# board.net
KiCad netlist of a schematic drawn in EAGLE
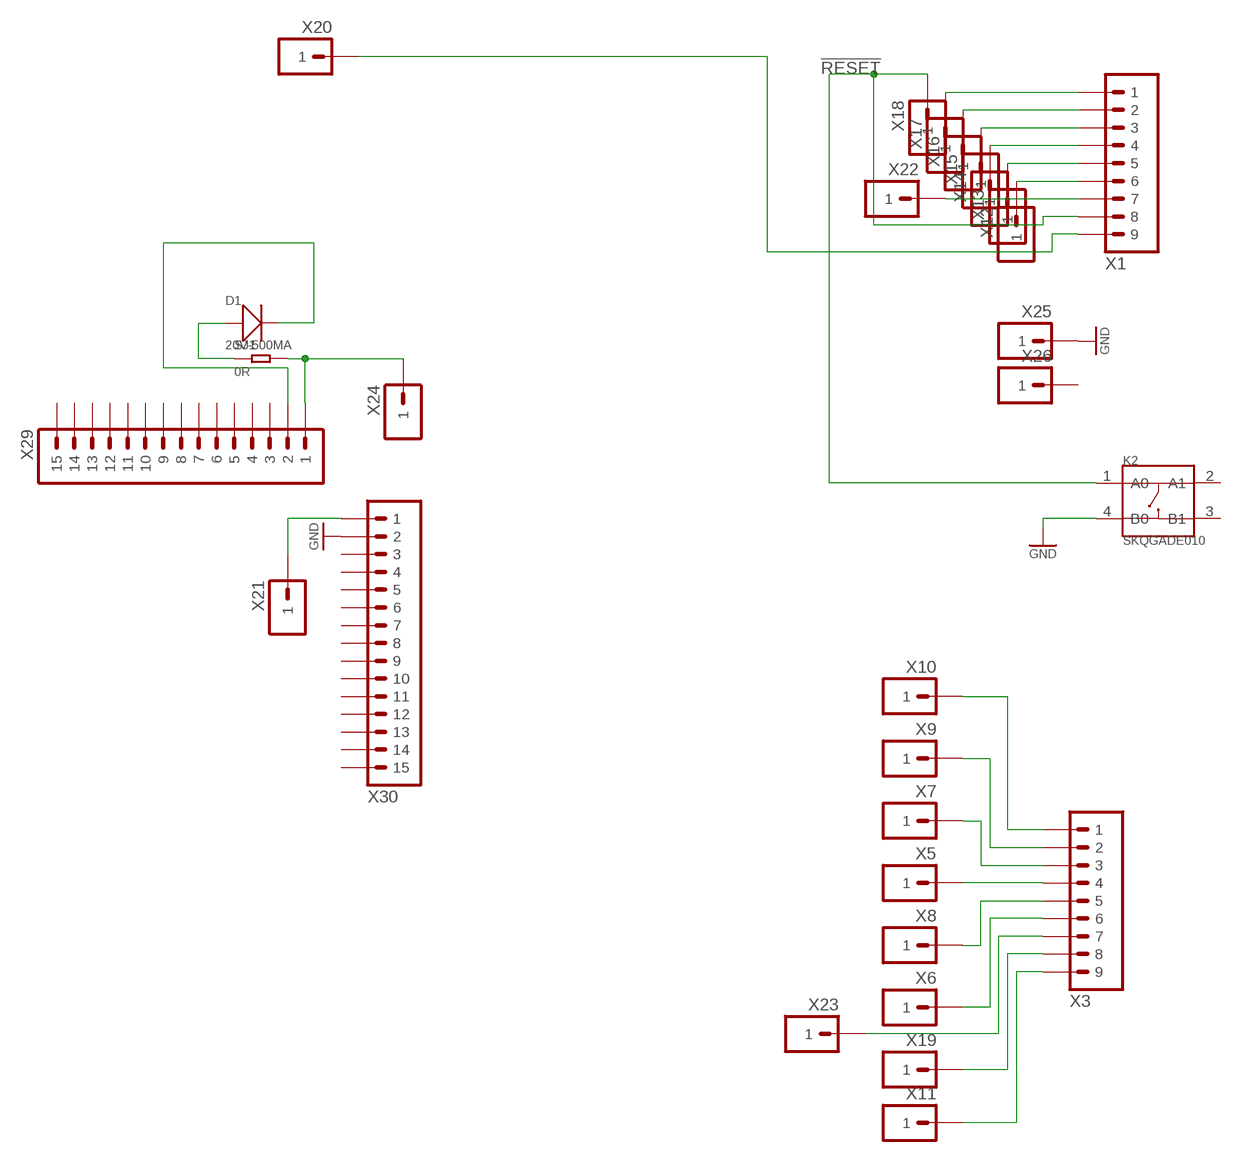
[diagram p0: schematic, sheet 1]

(export (version "E")
  (design (tool "Eeschema 10.0.6"))
  (components
    (comp (ref "D1")
      (value "20V-500MA")
      (footprint "eagle-import:SOD-123")
      (fields (field (name "MPN") "MBR0520LT1G"))
      (libsource (lib "eagle-import") (part "SMD-DIODE-SCHOTTKY-20V-500MA(SOD-123)"))
    )
    (comp (ref "K2")
      (value "SKQGADE010")
      (footprint "eagle-import:SW4-SMD-5.2X5.2X1.5MM")
      (libsource (lib "eagle-import") (part "SMD-SWITCH-TOP-260GF(4P-D5.2MM)"))
    )
    (comp (ref "SJ1")
      (value "0R")
      (footprint "eagle-import:R0805")
      (fields (field (name "MPN") "RC0805FR-071K5L"))
      (libsource (lib "eagle-import") (part "SMD-RES-1.5K-1%-1/8W(0805)"))
    )
    (comp (ref "X1")
      (value "9P1/MIN_NOSILK")
      (footprint "eagle-import:HEADER_1X9_1_MIN_NOSILK")
      (libsource (lib "eagle-import") (part "9P1/MIN_NOSILK"))
    )
    (comp (ref "X3")
      (value "9P1/MIN_NOSILK")
      (footprint "eagle-import:HEADER_1X9_1_MIN_NOSILK")
      (libsource (lib "eagle-import") (part "9P1/MIN_NOSILK"))
    )
    (comp (ref "X5")
      (value "1P")
      (footprint "eagle-import:1P_X")
      (libsource (lib "eagle-import") (part "1P"))
    )
    (comp (ref "X6")
      (value "1P")
      (footprint "eagle-import:1P_X")
      (libsource (lib "eagle-import") (part "1P"))
    )
    (comp (ref "X7")
      (value "1P")
      (footprint "eagle-import:1P_X")
      (libsource (lib "eagle-import") (part "1P"))
    )
    (comp (ref "X8")
      (value "1P")
      (footprint "eagle-import:1P_X")
      (libsource (lib "eagle-import") (part "1P"))
    )
    (comp (ref "X9")
      (value "1P")
      (footprint "eagle-import:1P_X")
      (libsource (lib "eagle-import") (part "1P"))
    )
    (comp (ref "X10")
      (value "1P")
      (footprint "eagle-import:1P_X")
      (libsource (lib "eagle-import") (part "1P"))
    )
    (comp (ref "X11")
      (value "1P1/MIN_SILK2")
      (footprint "eagle-import:HEADER_1X1_1_MIN_SILK2")
      (libsource (lib "eagle-import") (part "1P1/MIN_SILK2"))
    )
    (comp (ref "X12")
      (value "1P")
      (footprint "eagle-import:1P_X")
      (libsource (lib "eagle-import") (part "1P"))
    )
    (comp (ref "X13")
      (value "1P")
      (footprint "eagle-import:1P_X")
      (libsource (lib "eagle-import") (part "1P"))
    )
    (comp (ref "X14")
      (value "1P")
      (footprint "eagle-import:1P_X")
      (libsource (lib "eagle-import") (part "1P"))
    )
    (comp (ref "X15")
      (value "1P")
      (footprint "eagle-import:1P_X")
      (libsource (lib "eagle-import") (part "1P"))
    )
    (comp (ref "X16")
      (value "1P")
      (footprint "eagle-import:1P_X")
      (libsource (lib "eagle-import") (part "1P"))
    )
    (comp (ref "X17")
      (value "1P")
      (footprint "eagle-import:1P_X")
      (libsource (lib "eagle-import") (part "1P"))
    )
    (comp (ref "X18")
      (value "1P")
      (footprint "eagle-import:1P_X")
      (libsource (lib "eagle-import") (part "1P"))
    )
    (comp (ref "X19")
      (value "1P1/MIN_SILK2")
      (footprint "eagle-import:HEADER_1X1_1_MIN_SILK2")
      (libsource (lib "eagle-import") (part "1P1/MIN_SILK2"))
    )
    (comp (ref "X20")
      (value "1P1/MIN_SILK2")
      (footprint "eagle-import:HEADER_1X1_1_MIN_SILK2")
      (libsource (lib "eagle-import") (part "1P1/MIN_SILK2"))
    )
    (comp (ref "X21")
      (value "1P1/MIN_SILK2")
      (footprint "eagle-import:HEADER_1X1_1_MIN_SILK2")
      (libsource (lib "eagle-import") (part "1P1/MIN_SILK2"))
    )
    (comp (ref "X22")
      (value "1P1/MIN_SILK2")
      (footprint "eagle-import:HEADER_1X1_1_MIN_SILK2")
      (libsource (lib "eagle-import") (part "1P1/MIN_SILK2"))
    )
    (comp (ref "X23")
      (value "1P1/MIN_SILK2")
      (footprint "eagle-import:HEADER_1X1_1_MIN_SILK2")
      (libsource (lib "eagle-import") (part "1P1/MIN_SILK2"))
    )
    (comp (ref "X24")
      (value "1P1/MIN_SILK2")
      (footprint "eagle-import:HEADER_1X1_1_MIN_SILK2")
      (libsource (lib "eagle-import") (part "1P1/MIN_SILK2"))
    )
    (comp (ref "X25")
      (value "1P")
      (footprint "eagle-import:1P_X")
      (libsource (lib "eagle-import") (part "1P"))
    )
    (comp (ref "X26")
      (value "1P")
      (footprint "eagle-import:1P_X")
      (libsource (lib "eagle-import") (part "1P"))
    )
    (comp (ref "X29")
      (value "15P1/MIN_NOSILK")
      (footprint "eagle-import:HEADER_1X15_1_MIN_NOSILK")
      (libsource (lib "eagle-import") (part "15P1/MIN_NOSILK"))
    )
    (comp (ref "X30")
      (value "15P1/MIN_NOSILK")
      (footprint "eagle-import:HEADER_1X15_1_MIN_NOSILK")
      (libsource (lib "eagle-import") (part "15P1/MIN_NOSILK"))
    )
  )
  (nets
    (net (code "1") (name "/~{RESET}") (class "Default")
      (node (ref "K2") (pin "1") (pinfunction "A0_1") (pintype "bidirectional"))
      (node (ref "X1") (pin "8") (pinfunction "8_8") (pintype "passive"))
      (node (ref "X18") (pin "P$1") (pinfunction "1_P$1") (pintype "passive"))
    )
    (net (code "2") (name "GND") (class "Default")
      (node (ref "K2") (pin "4") (pinfunction "B0_4") (pintype "bidirectional"))
      (node (ref "X25") (pin "P$1") (pinfunction "1_P$1") (pintype "passive"))
      (node (ref "X30") (pin "2") (pinfunction "2_2") (pintype "passive"))
    )
    (net (code "3") (name "Net-(D1-Pad+)") (class "Default")
      (node (ref "D1") (pin "+") (pinfunction "+_+") (pintype "passive"))
      (node (ref "SJ1") (pin "1") (pinfunction "1_1") (pintype "passive"))
    )
    (net (code "4") (name "Net-(D1-Pad-)") (class "Default")
      (node (ref "D1") (pin "-") (pinfunction "-_-") (pintype "passive"))
      (node (ref "X29") (pin "2") (pinfunction "2_2") (pintype "passive"))
    )
    (net (code "5") (name "Net-(SJ1-Pad2)") (class "Default")
      (node (ref "SJ1") (pin "2") (pinfunction "2_2") (pintype "passive"))
      (node (ref "X24") (pin "1") (pinfunction "1_1") (pintype "passive"))
      (node (ref "X29") (pin "1") (pinfunction "1_1") (pintype "passive"))
    )
    (net (code "6") (name "Net-(X1-Pad7)") (class "Default")
      (node (ref "X1") (pin "7") (pinfunction "7_7") (pintype "passive"))
      (node (ref "X22") (pin "1") (pinfunction "1_1") (pintype "passive"))
    )
    (net (code "7") (name "Net-(X1-Pad9)") (class "Default")
      (node (ref "X1") (pin "9") (pinfunction "9_9") (pintype "passive"))
      (node (ref "X20") (pin "1") (pinfunction "1_1") (pintype "passive"))
    )
    (net (code "8") (name "Net-(X5-1)") (class "Default")
      (node (ref "X3") (pin "4") (pinfunction "4_4") (pintype "passive"))
      (node (ref "X5") (pin "P$1") (pinfunction "1_P$1") (pintype "passive"))
    )
    (net (code "9") (name "Net-(X6-1)") (class "Default")
      (node (ref "X3") (pin "6") (pinfunction "6_6") (pintype "passive"))
      (node (ref "X6") (pin "P$1") (pinfunction "1_P$1") (pintype "passive"))
    )
    (net (code "10") (name "Net-(X7-1)") (class "Default")
      (node (ref "X3") (pin "3") (pinfunction "3_3") (pintype "passive"))
      (node (ref "X7") (pin "P$1") (pinfunction "1_P$1") (pintype "passive"))
    )
    (net (code "11") (name "Net-(X8-1)") (class "Default")
      (node (ref "X3") (pin "5") (pinfunction "5_5") (pintype "passive"))
      (node (ref "X8") (pin "P$1") (pinfunction "1_P$1") (pintype "passive"))
    )
    (net (code "12") (name "Net-(X9-1)") (class "Default")
      (node (ref "X3") (pin "2") (pinfunction "2_2") (pintype "passive"))
      (node (ref "X9") (pin "P$1") (pinfunction "1_P$1") (pintype "passive"))
    )
    (net (code "13") (name "Net-(X10-1)") (class "Default")
      (node (ref "X10") (pin "P$1") (pinfunction "1_P$1") (pintype "passive"))
      (node (ref "X3") (pin "1") (pinfunction "1_1") (pintype "passive"))
    )
    (net (code "14") (name "Net-(X11-Pad1)") (class "Default")
      (node (ref "X11") (pin "1") (pinfunction "1_1") (pintype "passive"))
      (node (ref "X3") (pin "9") (pinfunction "9_9") (pintype "passive"))
    )
    (net (code "15") (name "Net-(X12-1)") (class "Default")
      (node (ref "X1") (pin "6") (pinfunction "6_6") (pintype "passive"))
      (node (ref "X12") (pin "P$1") (pinfunction "1_P$1") (pintype "passive"))
    )
    (net (code "16") (name "Net-(X13-1)") (class "Default")
      (node (ref "X1") (pin "5") (pinfunction "5_5") (pintype "passive"))
      (node (ref "X13") (pin "P$1") (pinfunction "1_P$1") (pintype "passive"))
    )
    (net (code "17") (name "Net-(X14-1)") (class "Default")
      (node (ref "X1") (pin "4") (pinfunction "4_4") (pintype "passive"))
      (node (ref "X14") (pin "P$1") (pinfunction "1_P$1") (pintype "passive"))
    )
    (net (code "18") (name "Net-(X15-1)") (class "Default")
      (node (ref "X1") (pin "3") (pinfunction "3_3") (pintype "passive"))
      (node (ref "X15") (pin "P$1") (pinfunction "1_P$1") (pintype "passive"))
    )
    (net (code "19") (name "Net-(X16-1)") (class "Default")
      (node (ref "X1") (pin "2") (pinfunction "2_2") (pintype "passive"))
      (node (ref "X16") (pin "P$1") (pinfunction "1_P$1") (pintype "passive"))
    )
    (net (code "20") (name "Net-(X17-1)") (class "Default")
      (node (ref "X1") (pin "1") (pinfunction "1_1") (pintype "passive"))
      (node (ref "X17") (pin "P$1") (pinfunction "1_P$1") (pintype "passive"))
    )
    (net (code "21") (name "Net-(X19-Pad1)") (class "Default")
      (node (ref "X19") (pin "1") (pinfunction "1_1") (pintype "passive"))
      (node (ref "X3") (pin "8") (pinfunction "8_8") (pintype "passive"))
    )
    (net (code "22") (name "Net-(X21-Pad1)") (class "Default")
      (node (ref "X21") (pin "1") (pinfunction "1_1") (pintype "passive"))
      (node (ref "X30") (pin "1") (pinfunction "1_1") (pintype "passive"))
    )
    (net (code "23") (name "Net-(X23-Pad1)") (class "Default")
      (node (ref "X23") (pin "1") (pinfunction "1_1") (pintype "passive"))
      (node (ref "X3") (pin "7") (pinfunction "7_7") (pintype "passive"))
    )
    (net (code "24") (name "unconnected-(K2-A1-Pad2)") (class "Default")
      (node (ref "K2") (pin "2") (pinfunction "A1_2") (pintype "bidirectional"))
    )
    (net (code "25") (name "unconnected-(K2-B1-Pad3)") (class "Default")
      (node (ref "K2") (pin "3") (pinfunction "B1_3") (pintype "bidirectional"))
    )
    (net (code "26") (name "unconnected-(X26-1-PadP$1)") (class "Default")
      (node (ref "X26") (pin "P$1") (pinfunction "1_P$1") (pintype "passive"))
    )
    (net (code "27") (name "unconnected-(X29-Pad3)") (class "Default")
      (node (ref "X29") (pin "3") (pinfunction "3_3") (pintype "passive"))
    )
    (net (code "28") (name "unconnected-(X29-Pad4)") (class "Default")
      (node (ref "X29") (pin "4") (pinfunction "4_4") (pintype "passive"))
    )
    (net (code "29") (name "unconnected-(X29-Pad5)") (class "Default")
      (node (ref "X29") (pin "5") (pinfunction "5_5") (pintype "passive"))
    )
    (net (code "30") (name "unconnected-(X29-Pad6)") (class "Default")
      (node (ref "X29") (pin "6") (pinfunction "6_6") (pintype "passive"))
    )
    (net (code "31") (name "unconnected-(X29-Pad7)") (class "Default")
      (node (ref "X29") (pin "7") (pinfunction "7_7") (pintype "passive"))
    )
    (net (code "32") (name "unconnected-(X29-Pad8)") (class "Default")
      (node (ref "X29") (pin "8") (pinfunction "8_8") (pintype "passive"))
    )
    (net (code "33") (name "unconnected-(X29-Pad9)") (class "Default")
      (node (ref "X29") (pin "9") (pinfunction "9_9") (pintype "passive"))
    )
    (net (code "34") (name "unconnected-(X29-Pad10)") (class "Default")
      (node (ref "X29") (pin "10") (pinfunction "10_10") (pintype "passive"))
    )
    (net (code "35") (name "unconnected-(X29-Pad11)") (class "Default")
      (node (ref "X29") (pin "11") (pinfunction "11_11") (pintype "passive"))
    )
    (net (code "36") (name "unconnected-(X29-Pad12)") (class "Default")
      (node (ref "X29") (pin "12") (pinfunction "12_12") (pintype "passive"))
    )
    (net (code "37") (name "unconnected-(X29-Pad13)") (class "Default")
      (node (ref "X29") (pin "13") (pinfunction "13_13") (pintype "passive"))
    )
    (net (code "38") (name "unconnected-(X29-Pad14)") (class "Default")
      (node (ref "X29") (pin "14") (pinfunction "14_14") (pintype "passive"))
    )
    (net (code "39") (name "unconnected-(X29-Pad15)") (class "Default")
      (node (ref "X29") (pin "15") (pinfunction "15_15") (pintype "passive"))
    )
    (net (code "40") (name "unconnected-(X30-Pad3)") (class "Default")
      (node (ref "X30") (pin "3") (pinfunction "3_3") (pintype "passive"))
    )
    (net (code "41") (name "unconnected-(X30-Pad4)") (class "Default")
      (node (ref "X30") (pin "4") (pinfunction "4_4") (pintype "passive"))
    )
    (net (code "42") (name "unconnected-(X30-Pad5)") (class "Default")
      (node (ref "X30") (pin "5") (pinfunction "5_5") (pintype "passive"))
    )
    (net (code "43") (name "unconnected-(X30-Pad6)") (class "Default")
      (node (ref "X30") (pin "6") (pinfunction "6_6") (pintype "passive"))
    )
    (net (code "44") (name "unconnected-(X30-Pad7)") (class "Default")
      (node (ref "X30") (pin "7") (pinfunction "7_7") (pintype "passive"))
    )
    (net (code "45") (name "unconnected-(X30-Pad8)") (class "Default")
      (node (ref "X30") (pin "8") (pinfunction "8_8") (pintype "passive"))
    )
    (net (code "46") (name "unconnected-(X30-Pad9)") (class "Default")
      (node (ref "X30") (pin "9") (pinfunction "9_9") (pintype "passive"))
    )
    (net (code "47") (name "unconnected-(X30-Pad10)") (class "Default")
      (node (ref "X30") (pin "10") (pinfunction "10_10") (pintype "passive"))
    )
    (net (code "48") (name "unconnected-(X30-Pad11)") (class "Default")
      (node (ref "X30") (pin "11") (pinfunction "11_11") (pintype "passive"))
    )
    (net (code "49") (name "unconnected-(X30-Pad12)") (class "Default")
      (node (ref "X30") (pin "12") (pinfunction "12_12") (pintype "passive"))
    )
    (net (code "50") (name "unconnected-(X30-Pad13)") (class "Default")
      (node (ref "X30") (pin "13") (pinfunction "13_13") (pintype "passive"))
    )
    (net (code "51") (name "unconnected-(X30-Pad14)") (class "Default")
      (node (ref "X30") (pin "14") (pinfunction "14_14") (pintype "passive"))
    )
    (net (code "52") (name "unconnected-(X30-Pad15)") (class "Default")
      (node (ref "X30") (pin "15") (pinfunction "15_15") (pintype "passive"))
    )
  )
)
